# Fan_Control_Module.net
KiCad netlist of a schematic drawn in Altium Designer
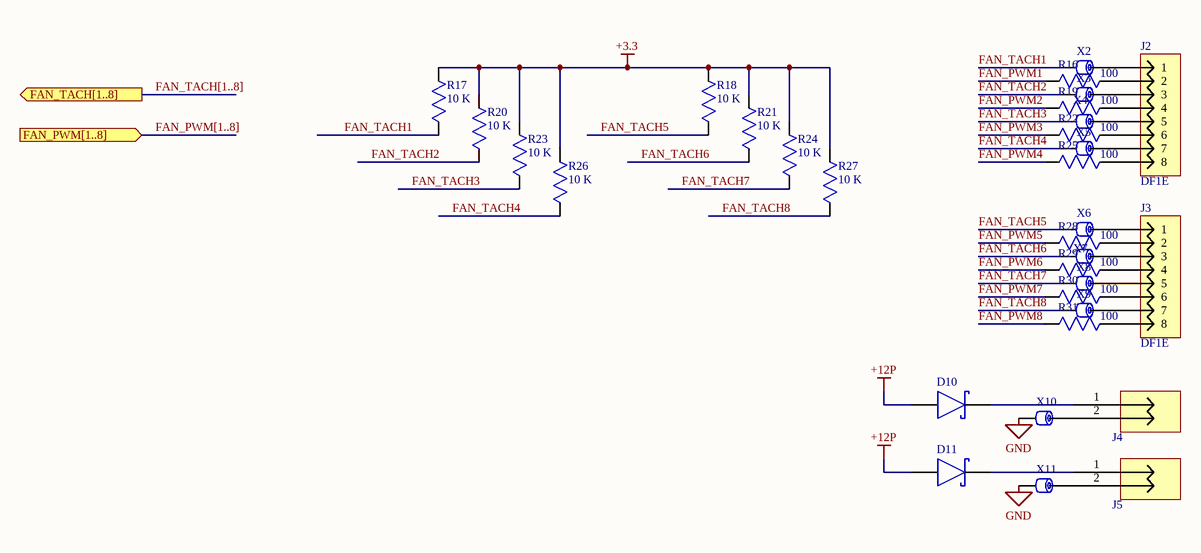
[diagram p0: Fan Control Module.SchDoc]

(export (version "E")
  (design (tool "Eeschema 10.0.6"))
  (components
    (comp (ref "D10")
      (value "STPS20L15G-TR")
      (footprint "D2PAK-D")
      (description "DIODE SCHOTTKY 20A 15V D2PAK")
      (fields (field (name "MANUFACTURER") "STMicro") (field (name "SVP CREATOR") "Jonathan Nutzmann"))
      (libsource (lib "c3_SchLib") (part "D_Schottky_20A_15V_D2PAK"))
    )
    (comp (ref "D11")
      (value "STPS20L15G-TR")
      (footprint "D2PAK-D")
      (description "DIODE SCHOTTKY 20A 15V D2PAK")
      (fields (field (name "MANUFACTURER") "STMicro") (field (name "SVP CREATOR") "Jonathan Nutzmann"))
      (libsource (lib "c3_SchLib") (part "D_Schottky_20A_15V_D2PAK"))
    )
    (comp (ref "J2")
      (value "DF1E")
      (footprint "DF1EC-8P-2.5DSA")
      (description "9-pin Hirose")
      (fields
        (field (name "MANUFACTURER") "Hirose Electric Co Ltd")
        (field (name "Comment") "DF1E 5-pin Male Header")
        (field (name "SVP CREATOR") "Adam Shea")
      )
      (libsource (lib "Hirose") (part "DF1E_8_S"))
    )
    (comp (ref "J3")
      (value "DF1E")
      (footprint "DF1EC-8P-2.5DSA")
      (description "9-pin Hirose")
      (fields
        (field (name "MANUFACTURER") "Hirose Electric Co Ltd")
        (field (name "Comment") "DF1E 5-pin Male Header")
        (field (name "SVP CREATOR") "Adam Shea")
      )
      (libsource (lib "Hirose") (part "DF1E_8_S"))
    )
    (comp (ref "J4")
      (value "J_PHOENIX_2M_5.08")
      (footprint "PHX2UP")
      (description "2 Pin From Motor")
      (libsource (lib "c3_SchLib") (part "J_PHOENIX_2M_5.08"))
    )
    (comp (ref "J5")
      (value "J_PHOENIX_2M_5.08")
      (footprint "PHX2UP")
      (description "2 Pin From Motor")
      (libsource (lib "c3_SchLib") (part "J_PHOENIX_2M_5.08"))
    )
    (comp (ref "R16")
      (value "100")
      (footprint "0603_res")
      (description "RES 0603")
      (libsource (lib "Nutz") (part "R_0603"))
    )
    (comp (ref "R17")
      (value "10 K")
      (footprint "0603_res")
      (description "RES 0603")
      (libsource (lib "Nutz") (part "R_0603"))
    )
    (comp (ref "R18")
      (value "10 K")
      (footprint "0603_res")
      (description "RES 0603")
      (libsource (lib "Nutz") (part "R_0603"))
    )
    (comp (ref "R19")
      (value "100")
      (footprint "0603_res")
      (description "RES 0603")
      (libsource (lib "Nutz") (part "R_0603"))
    )
    (comp (ref "R20")
      (value "10 K")
      (footprint "0603_res")
      (description "RES 0603")
      (libsource (lib "Nutz") (part "R_0603"))
    )
    (comp (ref "R21")
      (value "10 K")
      (footprint "0603_res")
      (description "RES 0603")
      (libsource (lib "Nutz") (part "R_0603"))
    )
    (comp (ref "R22")
      (value "100")
      (footprint "0603_res")
      (description "RES 0603")
      (libsource (lib "Nutz") (part "R_0603"))
    )
    (comp (ref "R23")
      (value "10 K")
      (footprint "0603_res")
      (description "RES 0603")
      (libsource (lib "Nutz") (part "R_0603"))
    )
    (comp (ref "R24")
      (value "10 K")
      (footprint "0603_res")
      (description "RES 0603")
      (libsource (lib "Nutz") (part "R_0603"))
    )
    (comp (ref "R25")
      (value "100")
      (footprint "0603_res")
      (description "RES 0603")
      (libsource (lib "Nutz") (part "R_0603"))
    )
    (comp (ref "R26")
      (value "10 K")
      (footprint "0603_res")
      (description "RES 0603")
      (libsource (lib "Nutz") (part "R_0603"))
    )
    (comp (ref "R27")
      (value "10 K")
      (footprint "0603_res")
      (description "RES 0603")
      (libsource (lib "Nutz") (part "R_0603"))
    )
    (comp (ref "R28")
      (value "100")
      (footprint "0603_res")
      (description "RES 0603")
      (libsource (lib "Nutz") (part "R_0603"))
    )
    (comp (ref "R29")
      (value "100")
      (footprint "0603_res")
      (description "RES 0603")
      (libsource (lib "Nutz") (part "R_0603"))
    )
    (comp (ref "R30")
      (value "100")
      (footprint "0603_res")
      (description "RES 0603")
      (libsource (lib "Nutz") (part "R_0603"))
    )
    (comp (ref "R31")
      (value "100")
      (footprint "0603_res")
      (description "RES 0603")
      (libsource (lib "Nutz") (part "R_0603"))
    )
    (comp (ref "X2")
      (value "0603")
      (footprint "0603_res")
      (description "FERRITE 0603")
      (libsource (lib "Nutz") (part "X_0603_FERRITE"))
    )
    (comp (ref "X3")
      (value "0603")
      (footprint "0603_res")
      (description "FERRITE 0603")
      (libsource (lib "Nutz") (part "X_0603_FERRITE"))
    )
    (comp (ref "X4")
      (value "0603")
      (footprint "0603_res")
      (description "FERRITE 0603")
      (libsource (lib "Nutz") (part "X_0603_FERRITE"))
    )
    (comp (ref "X5")
      (value "0603")
      (footprint "0603_res")
      (description "FERRITE 0603")
      (libsource (lib "Nutz") (part "X_0603_FERRITE"))
    )
    (comp (ref "X6")
      (value "0603")
      (footprint "0603_res")
      (description "FERRITE 0603")
      (libsource (lib "Nutz") (part "X_0603_FERRITE"))
    )
    (comp (ref "X7")
      (value "0603")
      (footprint "0603_res")
      (description "FERRITE 0603")
      (libsource (lib "Nutz") (part "X_0603_FERRITE"))
    )
    (comp (ref "X8")
      (value "0603")
      (footprint "0603_res")
      (description "FERRITE 0603")
      (libsource (lib "Nutz") (part "X_0603_FERRITE"))
    )
    (comp (ref "X9")
      (value "0603")
      (footprint "0603_res")
      (description "FERRITE 0603")
      (libsource (lib "Nutz") (part "X_0603_FERRITE"))
    )
    (comp (ref "X10")
      (value "Ferrite Bead")
      (footprint "28F0181-1SR-10")
      (description "FERRITE 10A 115 OHMS SMD")
      (fields (field (name "MANUFACTURER") "Laird-Signal Integrity Products"))
      (libsource (lib "c3_SchLib") (part "X_FERRITE_10A_3318"))
    )
    (comp (ref "X11")
      (value "Ferrite Bead")
      (footprint "28F0181-1SR-10")
      (description "FERRITE 10A 115 OHMS SMD")
      (fields (field (name "MANUFACTURER") "Laird-Signal Integrity Products"))
      (libsource (lib "c3_SchLib") (part "X_FERRITE_10A_3318"))
    )
  )
  (nets
    (net (code "1") (name "+3.3") (class "Default")
      (node (ref "R17") (pin "1") (pinfunction "1_1") (pintype "passive"))
      (node (ref "R18") (pin "1") (pinfunction "1_1") (pintype "passive"))
      (node (ref "R20") (pin "1") (pinfunction "1_1") (pintype "passive"))
      (node (ref "R21") (pin "1") (pinfunction "1_1") (pintype "passive"))
      (node (ref "R23") (pin "1") (pinfunction "1_1") (pintype "passive"))
      (node (ref "R24") (pin "1") (pinfunction "1_1") (pintype "passive"))
      (node (ref "R26") (pin "1") (pinfunction "1_1") (pintype "passive"))
      (node (ref "R27") (pin "1") (pinfunction "1_1") (pintype "passive"))
    )
    (net (code "2") (name "+12P") (class "Default")
      (node (ref "D10") (pin "A") (pinfunction "A_A") (pintype "passive"))
      (node (ref "D11") (pin "A") (pinfunction "A_A") (pintype "passive"))
    )
    (net (code "3") (name "/FAN_PWM1") (class "Default")
      (node (ref "R16") (pin "2") (pinfunction "2_2") (pintype "passive"))
    )
    (net (code "4") (name "/FAN_PWM2") (class "Default")
      (node (ref "R19") (pin "2") (pinfunction "2_2") (pintype "passive"))
    )
    (net (code "5") (name "/FAN_PWM3") (class "Default")
      (node (ref "R22") (pin "2") (pinfunction "2_2") (pintype "passive"))
    )
    (net (code "6") (name "/FAN_PWM4") (class "Default")
      (node (ref "R25") (pin "2") (pinfunction "2_2") (pintype "passive"))
    )
    (net (code "7") (name "/FAN_PWM5") (class "Default")
      (node (ref "R28") (pin "2") (pinfunction "2_2") (pintype "passive"))
    )
    (net (code "8") (name "/FAN_PWM6") (class "Default")
      (node (ref "R29") (pin "2") (pinfunction "2_2") (pintype "passive"))
    )
    (net (code "9") (name "/FAN_PWM7") (class "Default")
      (node (ref "R30") (pin "2") (pinfunction "2_2") (pintype "passive"))
    )
    (net (code "10") (name "/FAN_PWM8") (class "Default")
      (node (ref "R31") (pin "2") (pinfunction "2_2") (pintype "passive"))
    )
    (net (code "12") (name "/FAN_TACH1") (class "Default")
      (node (ref "R17") (pin "2") (pinfunction "2_2") (pintype "passive"))
      (node (ref "X2") (pin "1") (pinfunction "1_1") (pintype "passive"))
    )
    (net (code "13") (name "/FAN_TACH2") (class "Default")
      (node (ref "R20") (pin "2") (pinfunction "2_2") (pintype "passive"))
      (node (ref "X3") (pin "1") (pinfunction "1_1") (pintype "passive"))
    )
    (net (code "14") (name "/FAN_TACH3") (class "Default")
      (node (ref "R23") (pin "2") (pinfunction "2_2") (pintype "passive"))
      (node (ref "X4") (pin "1") (pinfunction "1_1") (pintype "passive"))
    )
    (net (code "15") (name "/FAN_TACH4") (class "Default")
      (node (ref "R26") (pin "2") (pinfunction "2_2") (pintype "passive"))
      (node (ref "X5") (pin "1") (pinfunction "1_1") (pintype "passive"))
    )
    (net (code "16") (name "/FAN_TACH5") (class "Default")
      (node (ref "R18") (pin "2") (pinfunction "2_2") (pintype "passive"))
      (node (ref "X6") (pin "1") (pinfunction "1_1") (pintype "passive"))
    )
    (net (code "17") (name "/FAN_TACH6") (class "Default")
      (node (ref "R21") (pin "2") (pinfunction "2_2") (pintype "passive"))
      (node (ref "X7") (pin "1") (pinfunction "1_1") (pintype "passive"))
    )
    (net (code "18") (name "/FAN_TACH7") (class "Default")
      (node (ref "R24") (pin "2") (pinfunction "2_2") (pintype "passive"))
      (node (ref "X8") (pin "1") (pinfunction "1_1") (pintype "passive"))
    )
    (net (code "19") (name "/FAN_TACH8") (class "Default")
      (node (ref "R27") (pin "2") (pinfunction "2_2") (pintype "passive"))
      (node (ref "X9") (pin "1") (pinfunction "1_1") (pintype "passive"))
    )
    (net (code "21") (name "GND") (class "Default")
      (node (ref "X10") (pin "1") (pinfunction "1_1") (pintype "passive"))
      (node (ref "X11") (pin "1") (pinfunction "1_1") (pintype "passive"))
    )
    (net (code "22") (name "Net-(D10-PadK)") (class "Default")
      (node (ref "D10") (pin "K") (pinfunction "K_K") (pintype "passive"))
      (node (ref "J4") (pin "1") (pinfunction "1_1") (pintype "passive"))
    )
    (net (code "23") (name "Net-(D11-PadK)") (class "Default")
      (node (ref "D11") (pin "K") (pinfunction "K_K") (pintype "passive"))
      (node (ref "J5") (pin "1") (pinfunction "1_1") (pintype "passive"))
    )
    (net (code "24") (name "Net-(J2-Pad1)") (class "Default")
      (node (ref "J2") (pin "1") (pinfunction "1_1") (pintype "passive"))
      (node (ref "X2") (pin "2") (pinfunction "2_2") (pintype "passive"))
    )
    (net (code "25") (name "Net-(J2-Pad2)") (class "Default")
      (node (ref "J2") (pin "2") (pinfunction "2_2") (pintype "passive"))
      (node (ref "R16") (pin "1") (pinfunction "1_1") (pintype "passive"))
    )
    (net (code "26") (name "Net-(J2-Pad3)") (class "Default")
      (node (ref "J2") (pin "3") (pinfunction "3_3") (pintype "passive"))
      (node (ref "X3") (pin "2") (pinfunction "2_2") (pintype "passive"))
    )
    (net (code "27") (name "Net-(J2-Pad4)") (class "Default")
      (node (ref "J2") (pin "4") (pinfunction "4_4") (pintype "passive"))
      (node (ref "R19") (pin "1") (pinfunction "1_1") (pintype "passive"))
    )
    (net (code "28") (name "Net-(J2-Pad5)") (class "Default")
      (node (ref "J2") (pin "5") (pinfunction "5_5") (pintype "passive"))
      (node (ref "X4") (pin "2") (pinfunction "2_2") (pintype "passive"))
    )
    (net (code "29") (name "Net-(J2-Pad6)") (class "Default")
      (node (ref "J2") (pin "6") (pinfunction "6_6") (pintype "passive"))
      (node (ref "R22") (pin "1") (pinfunction "1_1") (pintype "passive"))
    )
    (net (code "30") (name "Net-(J2-Pad7)") (class "Default")
      (node (ref "J2") (pin "7") (pinfunction "7_7") (pintype "passive"))
      (node (ref "X5") (pin "2") (pinfunction "2_2") (pintype "passive"))
    )
    (net (code "31") (name "Net-(J2-Pad8)") (class "Default")
      (node (ref "J2") (pin "8") (pinfunction "8_8") (pintype "passive"))
      (node (ref "R25") (pin "1") (pinfunction "1_1") (pintype "passive"))
    )
    (net (code "32") (name "Net-(J3-Pad1)") (class "Default")
      (node (ref "J3") (pin "1") (pinfunction "1_1") (pintype "passive"))
      (node (ref "X6") (pin "2") (pinfunction "2_2") (pintype "passive"))
    )
    (net (code "33") (name "Net-(J3-Pad2)") (class "Default")
      (node (ref "J3") (pin "2") (pinfunction "2_2") (pintype "passive"))
      (node (ref "R28") (pin "1") (pinfunction "1_1") (pintype "passive"))
    )
    (net (code "34") (name "Net-(J3-Pad3)") (class "Default")
      (node (ref "J3") (pin "3") (pinfunction "3_3") (pintype "passive"))
      (node (ref "X7") (pin "2") (pinfunction "2_2") (pintype "passive"))
    )
    (net (code "35") (name "Net-(J3-Pad4)") (class "Default")
      (node (ref "J3") (pin "4") (pinfunction "4_4") (pintype "passive"))
      (node (ref "R29") (pin "1") (pinfunction "1_1") (pintype "passive"))
    )
    (net (code "36") (name "Net-(J3-Pad5)") (class "Default")
      (node (ref "J3") (pin "5") (pinfunction "5_5") (pintype "passive"))
      (node (ref "X8") (pin "2") (pinfunction "2_2") (pintype "passive"))
    )
    (net (code "37") (name "Net-(J3-Pad6)") (class "Default")
      (node (ref "J3") (pin "6") (pinfunction "6_6") (pintype "passive"))
      (node (ref "R30") (pin "1") (pinfunction "1_1") (pintype "passive"))
    )
    (net (code "38") (name "Net-(J3-Pad7)") (class "Default")
      (node (ref "J3") (pin "7") (pinfunction "7_7") (pintype "passive"))
      (node (ref "X9") (pin "2") (pinfunction "2_2") (pintype "passive"))
    )
    (net (code "39") (name "Net-(J3-Pad8)") (class "Default")
      (node (ref "J3") (pin "8") (pinfunction "8_8") (pintype "passive"))
      (node (ref "R31") (pin "1") (pinfunction "1_1") (pintype "passive"))
    )
    (net (code "40") (name "Net-(J4-Pad2)") (class "Default")
      (node (ref "J4") (pin "2") (pinfunction "2_2") (pintype "passive"))
      (node (ref "X10") (pin "2") (pinfunction "2_2") (pintype "passive"))
    )
    (net (code "41") (name "Net-(J5-Pad2)") (class "Default")
      (node (ref "J5") (pin "2") (pinfunction "2_2") (pintype "passive"))
      (node (ref "X11") (pin "2") (pinfunction "2_2") (pintype "passive"))
    )
  )
)
